# atmega8a.net
KiCad netlist of a schematic drawn in EAGLE
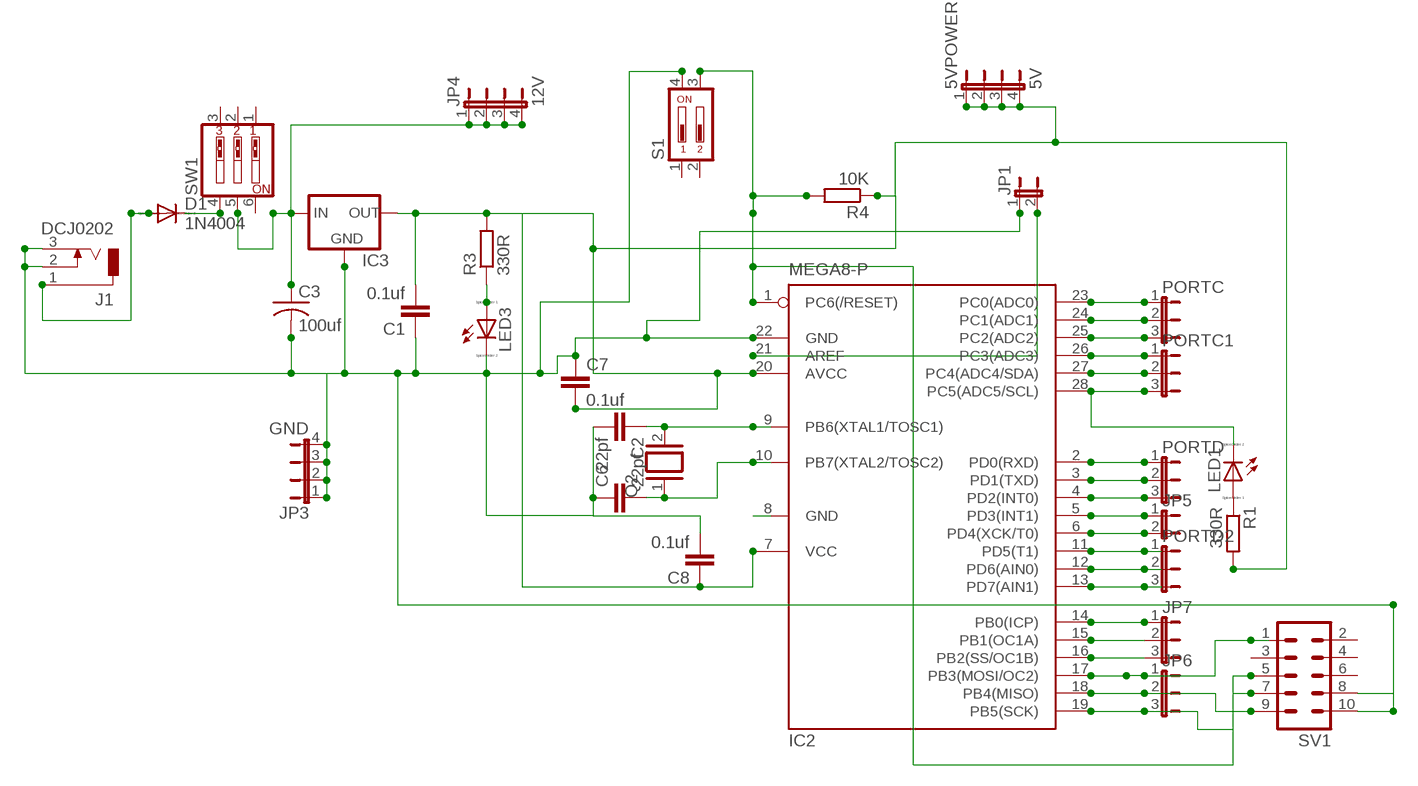
[diagram p0: schematic, sheet 1]

(export (version "E")
  (design (tool "Eeschema 10.0.6"))
  (components
    (comp (ref "5VPOWER")
      (value "5V")
      (footprint "eagle-import:JP4")
      (libsource (lib "eagle-import") (part "JP4E"))
    )
    (comp (ref "C1")
      (value "0.1uf")
      (footprint "eagle-import:C2.5-3")
      (libsource (lib "eagle-import") (part "C2,5-3"))
    )
    (comp (ref "C2")
      (value "22pf")
      (footprint "eagle-import:C2.5-3")
      (libsource (lib "eagle-import") (part "C2,5-3"))
    )
    (comp (ref "C3")
      (value "100uf")
      (footprint "eagle-import:C025-025X050")
      (libsource (lib "eagle-import") (part "C-US025-025X050"))
    )
    (comp (ref "C6")
      (value "22pf")
      (footprint "eagle-import:C2.5-3")
      (libsource (lib "eagle-import") (part "C2,5-3"))
    )
    (comp (ref "C7")
      (value "0.1uf")
      (footprint "eagle-import:C2.5-3")
      (libsource (lib "eagle-import") (part "C2,5-3"))
    )
    (comp (ref "C8")
      (value "0.1uf")
      (footprint "eagle-import:C2.5-3")
      (libsource (lib "eagle-import") (part "C2,5-3"))
    )
    (comp (ref "D1")
      (value "1N4004")
      (footprint "eagle-import:DO41-10")
      (libsource (lib "eagle-import") (part "1N4004"))
    )
    (comp (ref "IC2")
      (value "MEGA8-P")
      (footprint "eagle-import:DIL28-3")
      (libsource (lib "eagle-import") (part "MEGA8-P"))
    )
    (comp (ref "IC3")
      (value "78XXS")
      (footprint "eagle-import:78XXS")
      (libsource (lib "eagle-import") (part "78XXS"))
    )
    (comp (ref "J1")
      (value "DCJ0202")
      (footprint "eagle-import:DCJ0202")
      (libsource (lib "eagle-import") (part "DCJ0202"))
    )
    (comp (ref "JP1")
      (value "JP1E")
      (footprint "eagle-import:JP1")
      (libsource (lib "eagle-import") (part "JP1E"))
    )
    (comp (ref "JP3")
      (value "GND")
      (footprint "eagle-import:JP4")
      (libsource (lib "eagle-import") (part "JP4E"))
    )
    (comp (ref "JP4")
      (value "12V")
      (footprint "eagle-import:JP4")
      (libsource (lib "eagle-import") (part "JP4E"))
    )
    (comp (ref "JP5")
      (value "JP1E")
      (footprint "eagle-import:JP1")
      (libsource (lib "eagle-import") (part "JP1E"))
    )
    (comp (ref "JP6")
      (value "JP2W")
      (footprint "eagle-import:JP2W")
      (libsource (lib "eagle-import") (part "JP2W"))
    )
    (comp (ref "JP7")
      (value "JP2W")
      (footprint "eagle-import:JP2W")
      (libsource (lib "eagle-import") (part "JP2W"))
    )
    (comp (ref "LED1")
      (value "LED_ELD260")
      (footprint "eagle-import:LED_LD260")
      (libsource (lib "eagle-import") (part "LED_ELD260"))
    )
    (comp (ref "LED3")
      (value "LED_ELD260")
      (footprint "eagle-import:LED_LD260")
      (libsource (lib "eagle-import") (part "LED_ELD260"))
    )
    (comp (ref "PORTC")
      (value "JP2W")
      (footprint "eagle-import:JP2W")
      (libsource (lib "eagle-import") (part "JP2W"))
    )
    (comp (ref "PORTC1")
      (value "JP2W")
      (footprint "eagle-import:JP2W")
      (libsource (lib "eagle-import") (part "JP2W"))
    )
    (comp (ref "PORTD")
      (value "JP2W")
      (footprint "eagle-import:JP2W")
      (libsource (lib "eagle-import") (part "JP2W"))
    )
    (comp (ref "PORTD2")
      (value "JP2W")
      (footprint "eagle-import:JP2W")
      (libsource (lib "eagle-import") (part "JP2W"))
    )
    (comp (ref "Q2")
      (value "XTAL/S")
      (footprint "eagle-import:QS")
      (libsource (lib "eagle-import") (part "XTAL/S"))
    )
    (comp (ref "R1")
      (value "330R")
      (footprint "eagle-import:0207_7")
      (libsource (lib "eagle-import") (part "R-EU_0207/7"))
    )
    (comp (ref "R3")
      (value "330R")
      (footprint "eagle-import:0207_7")
      (libsource (lib "eagle-import") (part "R-EU_0207/7"))
    )
    (comp (ref "R4")
      (value "10K")
      (footprint "eagle-import:0207_7")
      (libsource (lib "eagle-import") (part "R-EU_0207/7"))
    )
    (comp (ref "S1")
      (value "SD4-02")
      (footprint "eagle-import:SD4-02")
      (libsource (lib "eagle-import") (part "SD4-02"))
    )
    (comp (ref "SV1")
      (value "MA05-2")
      (footprint "eagle-import:MA05-2")
      (libsource (lib "eagle-import") (part "MA05-2"))
    )
    (comp (ref "SW1")
      (value "SW_DIP-3")
      (footprint "eagle-import:EDG-03")
      (libsource (lib "eagle-import") (part "SW_DIP-3"))
    )
  )
  (nets
    (net (code "1") (name "Net-(C3-Pad1)") (class "Default")
      (node (ref "C3") (pin "1") (pinfunction "1_1") (pintype "passive"))
      (node (ref "IC3") (pin "IN") (pinfunction "IN_IN") (pintype "input"))
      (node (ref "JP4") (pin "1") (pinfunction "1_1") (pintype "passive"))
      (node (ref "JP4") (pin "2") (pinfunction "2_2") (pintype "passive"))
      (node (ref "JP4") (pin "3") (pinfunction "3_3") (pintype "passive"))
      (node (ref "JP4") (pin "4") (pinfunction "4_4") (pintype "passive"))
      (node (ref "SW1") (pin "5") (pinfunction "5_5") (pintype "passive"))
    )
    (net (code "2") (name "Net-(D1-PadA)") (class "Default")
      (node (ref "D1") (pin "A") (pinfunction "A_A") (pintype "passive"))
      (node (ref "J1") (pin "1") (pinfunction "1_1") (pintype "passive"))
    )
    (net (code "3") (name "Net-(D1-PadC)") (class "Default")
      (node (ref "D1") (pin "C") (pinfunction "C_C") (pintype "passive"))
      (node (ref "SW1") (pin "4") (pinfunction "4_4") (pintype "passive"))
    )
    (net (code "4") (name "Net-(IC2-AREF)") (class "Default")
      (node (ref "IC2") (pin "21") (pinfunction "AREF_21") (pintype "passive"))
      (node (ref "JP1") (pin "2") (pinfunction "2_2") (pintype "passive"))
    )
    (net (code "5") (name "Net-(IC2-AVCC)") (class "Default")
      (node (ref "5VPOWER") (pin "1") (pinfunction "1_1") (pintype "passive"))
      (node (ref "5VPOWER") (pin "2") (pinfunction "2_2") (pintype "passive"))
      (node (ref "5VPOWER") (pin "3") (pinfunction "3_3") (pintype "passive"))
      (node (ref "5VPOWER") (pin "4") (pinfunction "4_4") (pintype "passive"))
      (node (ref "C1") (pin "2") (pinfunction "2_2") (pintype "passive"))
      (node (ref "C7") (pin "2") (pinfunction "2_2") (pintype "passive"))
      (node (ref "C8") (pin "1") (pinfunction "1_1") (pintype "passive"))
      (node (ref "IC2") (pin "20") (pinfunction "AVCC_20") (pintype "power_in"))
      (node (ref "IC2") (pin "7") (pinfunction "VCC_7") (pintype "power_in"))
      (node (ref "IC3") (pin "OUT") (pinfunction "OUT_OUT") (pintype "passive"))
      (node (ref "R1") (pin "2") (pinfunction "2_2") (pintype "passive"))
      (node (ref "R3") (pin "2") (pinfunction "2_2") (pintype "passive"))
      (node (ref "R4") (pin "1") (pinfunction "1_1") (pintype "passive"))
    )
    (net (code "6") (name "Net-(IC2-PB0(ICP))") (class "Default")
      (node (ref "IC2") (pin "14") (pinfunction "PB0(ICP)_14") (pintype "bidirectional"))
      (node (ref "JP7") (pin "1") (pinfunction "1_1") (pintype "passive"))
    )
    (net (code "7") (name "Net-(IC2-PB1(OC1A))") (class "Default")
      (node (ref "IC2") (pin "15") (pinfunction "PB1(OC1A)_15") (pintype "bidirectional"))
      (node (ref "JP7") (pin "2") (pinfunction "2_2") (pintype "passive"))
    )
    (net (code "8") (name "Net-(IC2-PB2(SS{slash}OC1B))") (class "Default")
      (node (ref "IC2") (pin "16") (pinfunction "PB2(SS/OC1B)_16") (pintype "bidirectional"))
      (node (ref "JP7") (pin "3") (pinfunction "3_3") (pintype "passive"))
    )
    (net (code "9") (name "Net-(IC2-PB3(MOSI{slash}OC2))") (class "Default")
      (node (ref "IC2") (pin "17") (pinfunction "PB3(MOSI/OC2)_17") (pintype "bidirectional"))
      (node (ref "JP6") (pin "1") (pinfunction "1_1") (pintype "passive"))
      (node (ref "SV1") (pin "1") (pinfunction "1_1") (pintype "passive"))
    )
    (net (code "10") (name "Net-(IC2-PB4(MISO))") (class "Default")
      (node (ref "IC2") (pin "18") (pinfunction "PB4(MISO)_18") (pintype "bidirectional"))
      (node (ref "JP6") (pin "2") (pinfunction "2_2") (pintype "passive"))
      (node (ref "SV1") (pin "9") (pinfunction "9_9") (pintype "passive"))
    )
    (net (code "11") (name "Net-(IC2-PB5(SCK))") (class "Default")
      (node (ref "IC2") (pin "19") (pinfunction "PB5(SCK)_19") (pintype "bidirectional"))
      (node (ref "JP6") (pin "3") (pinfunction "3_3") (pintype "passive"))
      (node (ref "SV1") (pin "7") (pinfunction "7_7") (pintype "passive"))
    )
    (net (code "12") (name "Net-(IC2-PB6(XTAL1{slash}TOSC1))") (class "Default")
      (node (ref "C2") (pin "1") (pinfunction "1_1") (pintype "passive"))
      (node (ref "IC2") (pin "9") (pinfunction "PB6(XTAL1/TOSC1)_9") (pintype "bidirectional"))
      (node (ref "Q2") (pin "2") (pinfunction "2_2") (pintype "passive"))
    )
    (net (code "13") (name "Net-(IC2-PB7(XTAL2{slash}TOSC2))") (class "Default")
      (node (ref "C6") (pin "2") (pinfunction "2_2") (pintype "passive"))
      (node (ref "IC2") (pin "10") (pinfunction "PB7(XTAL2/TOSC2)_10") (pintype "bidirectional"))
      (node (ref "Q2") (pin "1") (pinfunction "1_1") (pintype "passive"))
    )
    (net (code "14") (name "Net-(IC2-PC0(ADC0))") (class "Default")
      (node (ref "IC2") (pin "23") (pinfunction "PC0(ADC0)_23") (pintype "bidirectional"))
      (node (ref "PORTC") (pin "1") (pinfunction "1_1") (pintype "passive"))
    )
    (net (code "15") (name "Net-(IC2-PC1(ADC1))") (class "Default")
      (node (ref "IC2") (pin "24") (pinfunction "PC1(ADC1)_24") (pintype "bidirectional"))
      (node (ref "PORTC") (pin "2") (pinfunction "2_2") (pintype "passive"))
    )
    (net (code "16") (name "Net-(IC2-PC2(ADC2))") (class "Default")
      (node (ref "IC2") (pin "25") (pinfunction "PC2(ADC2)_25") (pintype "bidirectional"))
      (node (ref "PORTC") (pin "3") (pinfunction "3_3") (pintype "passive"))
    )
    (net (code "17") (name "Net-(IC2-PC3(ADC3))") (class "Default")
      (node (ref "IC2") (pin "26") (pinfunction "PC3(ADC3)_26") (pintype "bidirectional"))
      (node (ref "PORTC1") (pin "1") (pinfunction "1_1") (pintype "passive"))
    )
    (net (code "18") (name "Net-(IC2-PC4(ADC4{slash}SDA))") (class "Default")
      (node (ref "IC2") (pin "27") (pinfunction "PC4(ADC4/SDA)_27") (pintype "bidirectional"))
      (node (ref "PORTC1") (pin "2") (pinfunction "2_2") (pintype "passive"))
    )
    (net (code "19") (name "Net-(IC2-PC5(ADC5{slash}SCL))") (class "Default")
      (node (ref "IC2") (pin "28") (pinfunction "PC5(ADC5/SCL)_28") (pintype "bidirectional"))
      (node (ref "LED1") (pin "K") (pinfunction "C_K") (pintype "passive"))
      (node (ref "PORTC1") (pin "3") (pinfunction "3_3") (pintype "passive"))
    )
    (net (code "20") (name "Net-(IC2-PC6({slash}RESET))") (class "Default")
      (node (ref "IC2") (pin "1") (pinfunction "PC6(/RESET)_1") (pintype "bidirectional"))
      (node (ref "R4") (pin "2") (pinfunction "2_2") (pintype "passive"))
      (node (ref "S1") (pin "3") (pinfunction "3_3") (pintype "passive"))
      (node (ref "SV1") (pin "5") (pinfunction "5_5") (pintype "passive"))
    )
    (net (code "21") (name "Net-(IC2-PD0(RXD))") (class "Default")
      (node (ref "IC2") (pin "2") (pinfunction "PD0(RXD)_2") (pintype "bidirectional"))
      (node (ref "PORTD") (pin "1") (pinfunction "1_1") (pintype "passive"))
    )
    (net (code "22") (name "Net-(IC2-PD1(TXD))") (class "Default")
      (node (ref "IC2") (pin "3") (pinfunction "PD1(TXD)_3") (pintype "bidirectional"))
      (node (ref "PORTD") (pin "2") (pinfunction "2_2") (pintype "passive"))
    )
    (net (code "23") (name "Net-(IC2-PD2(INT0))") (class "Default")
      (node (ref "IC2") (pin "4") (pinfunction "PD2(INT0)_4") (pintype "bidirectional"))
      (node (ref "PORTD") (pin "3") (pinfunction "3_3") (pintype "passive"))
    )
    (net (code "24") (name "Net-(IC2-PD3(INT1))") (class "Default")
      (node (ref "IC2") (pin "5") (pinfunction "PD3(INT1)_5") (pintype "bidirectional"))
      (node (ref "JP5") (pin "1") (pinfunction "1_1") (pintype "passive"))
    )
    (net (code "25") (name "Net-(IC2-PD4(XCK{slash}T0))") (class "Default")
      (node (ref "IC2") (pin "6") (pinfunction "PD4(XCK/T0)_6") (pintype "bidirectional"))
      (node (ref "JP5") (pin "2") (pinfunction "2_2") (pintype "passive"))
    )
    (net (code "26") (name "Net-(IC2-PD5(T1))") (class "Default")
      (node (ref "IC2") (pin "11") (pinfunction "PD5(T1)_11") (pintype "bidirectional"))
      (node (ref "PORTD2") (pin "1") (pinfunction "1_1") (pintype "passive"))
    )
    (net (code "27") (name "Net-(IC2-PD6(AIN0))") (class "Default")
      (node (ref "IC2") (pin "12") (pinfunction "PD6(AIN0)_12") (pintype "bidirectional"))
      (node (ref "PORTD2") (pin "2") (pinfunction "2_2") (pintype "passive"))
    )
    (net (code "28") (name "Net-(IC2-PD7(AIN1))") (class "Default")
      (node (ref "IC2") (pin "13") (pinfunction "PD7(AIN1)_13") (pintype "bidirectional"))
      (node (ref "PORTD2") (pin "3") (pinfunction "3_3") (pintype "passive"))
    )
    (net (code "29") (name "Net-(LED1-PadA)") (class "Default")
      (node (ref "LED1") (pin "A") (pinfunction "A_A") (pintype "passive"))
      (node (ref "R1") (pin "1") (pinfunction "1_1") (pintype "passive"))
    )
    (net (code "30") (name "Net-(LED3-C)") (class "Default")
      (node (ref "C1") (pin "1") (pinfunction "1_1") (pintype "passive"))
      (node (ref "C2") (pin "2") (pinfunction "2_2") (pintype "passive"))
      (node (ref "C3") (pin "2") (pinfunction "2_2") (pintype "passive"))
      (node (ref "C6") (pin "1") (pinfunction "1_1") (pintype "passive"))
      (node (ref "C7") (pin "1") (pinfunction "1_1") (pintype "passive"))
      (node (ref "C8") (pin "2") (pinfunction "2_2") (pintype "passive"))
      (node (ref "IC2") (pin "22") (pinfunction "GND_22") (pintype "power_in"))
      (node (ref "IC3") (pin "GND") (pinfunction "GND_GND") (pintype "input"))
      (node (ref "J1") (pin "2") (pinfunction "2_2") (pintype "passive"))
      (node (ref "J1") (pin "3") (pinfunction "3_3") (pintype "passive"))
      (node (ref "JP1") (pin "1") (pinfunction "1_1") (pintype "passive"))
      (node (ref "JP3") (pin "1") (pinfunction "1_1") (pintype "passive"))
      (node (ref "JP3") (pin "2") (pinfunction "2_2") (pintype "passive"))
      (node (ref "JP3") (pin "3") (pinfunction "3_3") (pintype "passive"))
      (node (ref "JP3") (pin "4") (pinfunction "4_4") (pintype "passive"))
      (node (ref "LED3") (pin "K") (pinfunction "C_K") (pintype "passive"))
      (node (ref "S1") (pin "4") (pinfunction "4_4") (pintype "passive"))
      (node (ref "SV1") (pin "10") (pinfunction "10_10") (pintype "passive"))
      (node (ref "SV1") (pin "8") (pinfunction "8_8") (pintype "passive"))
    )
    (net (code "31") (name "Net-(LED3-PadA)") (class "Default")
      (node (ref "LED3") (pin "A") (pinfunction "A_A") (pintype "passive"))
      (node (ref "R3") (pin "1") (pinfunction "1_1") (pintype "passive"))
    )
    (net (code "32") (name "unconnected-(IC2-GND-Pad8)") (class "Default")
      (node (ref "IC2") (pin "8") (pinfunction "GND_8") (pintype "power_in"))
    )
    (net (code "33") (name "unconnected-(S1-Pad1)") (class "Default")
      (node (ref "S1") (pin "1") (pinfunction "1_1") (pintype "passive"))
    )
    (net (code "34") (name "unconnected-(S1-Pad2)") (class "Default")
      (node (ref "S1") (pin "2") (pinfunction "2_2") (pintype "passive"))
    )
    (net (code "35") (name "unconnected-(SV1-Pad2)") (class "Default")
      (node (ref "SV1") (pin "2") (pinfunction "2_2") (pintype "passive"))
    )
    (net (code "36") (name "unconnected-(SV1-Pad3)") (class "Default")
      (node (ref "SV1") (pin "3") (pinfunction "3_3") (pintype "passive"))
    )
    (net (code "37") (name "unconnected-(SV1-Pad4)") (class "Default")
      (node (ref "SV1") (pin "4") (pinfunction "4_4") (pintype "passive"))
    )
    (net (code "38") (name "unconnected-(SV1-Pad6)") (class "Default")
      (node (ref "SV1") (pin "6") (pinfunction "6_6") (pintype "passive"))
    )
    (net (code "39") (name "unconnected-(SW1-Pad1)") (class "Default")
      (node (ref "SW1") (pin "1") (pinfunction "1_1") (pintype "passive"))
    )
    (net (code "40") (name "unconnected-(SW1-Pad2)") (class "Default")
      (node (ref "SW1") (pin "2") (pinfunction "2_2") (pintype "passive"))
    )
    (net (code "41") (name "unconnected-(SW1-Pad3)") (class "Default")
      (node (ref "SW1") (pin "3") (pinfunction "3_3") (pintype "passive"))
    )
    (net (code "42") (name "unconnected-(SW1-Pad6)") (class "Default")
      (node (ref "SW1") (pin "6") (pinfunction "6_6") (pintype "passive"))
    )
  )
)
